# Mosfets.net
KiCad netlist of a schematic drawn in Altium Designer
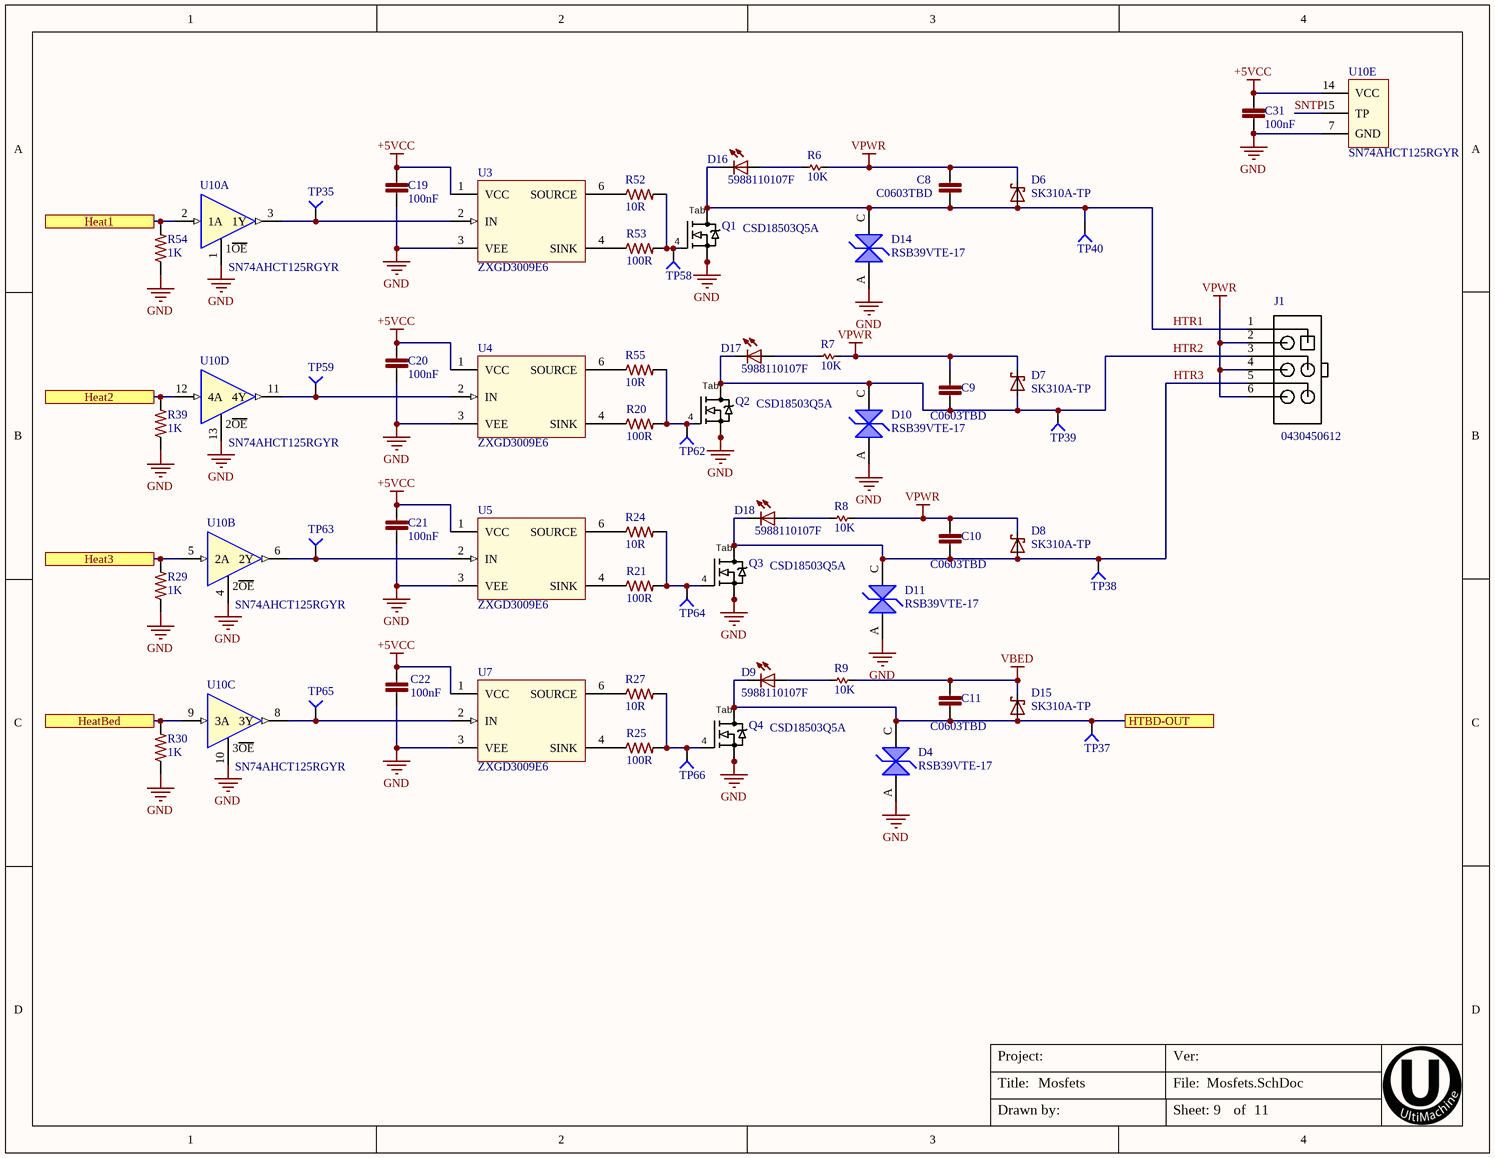
[diagram p0: Mosfets.SchDoc]

(export (version "E")
  (design (tool "Eeschema 10.0.6"))
  (components
    (comp (ref "C8")
      (value "C0603TBD")
      (footprint "C0603")
      (description "Capacitor Non Polarized")
      (fields (field (name "PART") "DNI-C0603TBD"))
      (libsource (lib "3Delight") (part "C0603TBD"))
    )
    (comp (ref "C9")
      (value "C0603TBD")
      (footprint "C0603")
      (description "Capacitor Non Polarized")
      (fields (field (name "PART") "DNI-C0603TBD"))
      (libsource (lib "3Delight") (part "C0603TBD"))
    )
    (comp (ref "C10")
      (value "C0603TBD")
      (footprint "C0603")
      (description "Capacitor Non Polarized")
      (fields (field (name "PART") "DNI-C0603TBD"))
      (libsource (lib "3Delight") (part "C0603TBD"))
    )
    (comp (ref "C11")
      (value "C0603TBD")
      (footprint "C0603")
      (description "Capacitor Non Polarized")
      (fields (field (name "PART") "DNI-C0603TBD"))
      (libsource (lib "3Delight") (part "C0603TBD"))
    )
    (comp (ref "C19")
      (value "100nF")
      (footprint "C0402")
      (description "CAP CER 0402 100nF 16V 10% X7R")
      (fields (field (name "MANUFACTURER") "Murata") (field (name "PART") "GRM155R71C104KA88D"))
      (libsource (lib "") (part "GRM155R71C104KA88D_1"))
    )
    (comp (ref "C20")
      (value "100nF")
      (footprint "C0402")
      (description "CAP CER 0402 100nF 16V 10% X7R")
      (fields (field (name "MANUFACTURER") "Murata") (field (name "PART") "GRM155R71C104KA88D"))
      (libsource (lib "") (part "GRM155R71C104KA88D_1"))
    )
    (comp (ref "C21")
      (value "100nF")
      (footprint "C0402")
      (description "CAP CER 0402 100nF 16V 10% X7R")
      (fields (field (name "MANUFACTURER") "Murata") (field (name "PART") "GRM155R71C104KA88D"))
      (libsource (lib "") (part "GRM155R71C104KA88D_1"))
    )
    (comp (ref "C22")
      (value "100nF")
      (footprint "C0402")
      (description "CAP CER 0402 100nF 16V 10% X7R")
      (fields (field (name "MANUFACTURER") "Murata") (field (name "PART") "GRM155R71C104KA88D"))
      (libsource (lib "3Delight") (part "GRM155R71C104KA88D"))
    )
    (comp (ref "C31")
      (value "100nF")
      (footprint "C0402")
      (description "CAP CER 0402 100nF 16V 10% X7R")
      (fields (field (name "MANUFACTURER") "Murata") (field (name "PART") "GRM155R71C104KA88D"))
      (libsource (lib "") (part "GRM155R71C104KA88D_1"))
    )
    (comp (ref "D4")
      (value "RSB39VTE-17")
      (footprint "SOD323-R")
      (description "DIODE TVS")
      (fields (field (name "MANUFACTURER") "Rohm") (field (name "TOLERANCE") "-NA-"))
      (libsource (lib "3Delight") (part "RSB39VTE-17"))
    )
    (comp (ref "D6")
      (value "SK310A-TP")
      (footprint "SMA-SM")
      (description "DIODE Schottky 3A SMA")
      (fields (field (name "MANUFACTURER") "MCC") (field (name "PART") "SK310A"))
      (libsource (lib "Archim_0.4") (part "SK310A"))
    )
    (comp (ref "D7")
      (value "SK310A-TP")
      (footprint "SMA-SM")
      (description "DIODE Schottky 3A SMA")
      (fields (field (name "MANUFACTURER") "MCC") (field (name "PART") "SK310A"))
      (libsource (lib "Archim_0.4") (part "SK310A"))
    )
    (comp (ref "D8")
      (value "SK310A-TP")
      (footprint "SMA-SM")
      (description "DIODE Schottky 3A SMA")
      (fields (field (name "MANUFACTURER") "MCC") (field (name "PART") "SK310A"))
      (libsource (lib "Archim_0.4") (part "SK310A"))
    )
    (comp (ref "D9")
      (value "Red")
      (footprint "LED2012120")
      (description "LED 0805 Red")
      (fields
        (field (name "MANUFACTURER") "Dialight")
        (field (name "PART") "5988110107F")
        (field (name "TOLERANCE") "-NA-")
      )
      (libsource (lib "3Delight") (part "5988110107F"))
    )
    (comp (ref "D10")
      (value "RSB39VTE-17")
      (footprint "SOD323-R")
      (description "DIODE TVS")
      (fields (field (name "MANUFACTURER") "Rohm") (field (name "TOLERANCE") "-NA-"))
      (libsource (lib "3Delight") (part "RSB39VTE-17"))
    )
    (comp (ref "D11")
      (value "RSB39VTE-17")
      (footprint "SOD323-R")
      (description "DIODE TVS")
      (fields (field (name "MANUFACTURER") "Rohm") (field (name "TOLERANCE") "-NA-"))
      (libsource (lib "3Delight") (part "RSB39VTE-17"))
    )
    (comp (ref "D14")
      (value "RSB39VTE-17")
      (footprint "SOD323-R")
      (description "DIODE TVS")
      (fields (field (name "MANUFACTURER") "Rohm") (field (name "TOLERANCE") "-NA-"))
      (libsource (lib "3Delight") (part "RSB39VTE-17"))
    )
    (comp (ref "D15")
      (value "SK310A-TP")
      (footprint "SMA-SM")
      (description "DIODE Schottky 3A SMA")
      (fields (field (name "MANUFACTURER") "MCC") (field (name "PART") "SK310A"))
      (libsource (lib "Archim_0.4") (part "SK310A"))
    )
    (comp (ref "D16")
      (value "Red")
      (footprint "LED2012120")
      (description "LED 0805 Red")
      (fields
        (field (name "MANUFACTURER") "Dialight")
        (field (name "PART") "5988110107F")
        (field (name "TOLERANCE") "-NA-")
      )
      (libsource (lib "3Delight") (part "5988110107F"))
    )
    (comp (ref "D17")
      (value "Red")
      (footprint "LED2012120")
      (description "LED 0805 Red")
      (fields
        (field (name "MANUFACTURER") "Dialight")
        (field (name "PART") "5988110107F")
        (field (name "TOLERANCE") "-NA-")
      )
      (libsource (lib "3Delight") (part "5988110107F"))
    )
    (comp (ref "D18")
      (value "Red")
      (footprint "LED2012120")
      (description "LED 0805 Red")
      (fields
        (field (name "MANUFACTURER") "Dialight")
        (field (name "PART") "5988110107F")
        (field (name "TOLERANCE") "-NA-")
      )
      (libsource (lib "3Delight") (part "5988110107F"))
    )
    (comp (ref "J1")
      (value "0430450612")
      (footprint "43045-0612")
      (description "Conn - 3mm Pitch Fixed")
      (fields (field (name "MANUFACTURER") "Molex"))
      (libsource (lib "Connectors") (part "Micro-Fit THT 6pos 3mm"))
    )
    (comp (ref "Q1")
      (value "CSD18503Q5A")
      (footprint "SOT669_Universal")
      (description "MOSFET N-CH 40V 100A 8VSON")
      (fields (field (name "MANUFACTURER") "TI"))
      (libsource (lib "Transistors") (part "CSD18503Q5A"))
    )
    (comp (ref "Q2")
      (value "CSD18503Q5A")
      (footprint "SOT669_Universal")
      (description "MOSFET N-CH 40V 100A 8VSON")
      (fields (field (name "MANUFACTURER") "TI"))
      (libsource (lib "Transistors") (part "CSD18503Q5A"))
    )
    (comp (ref "Q3")
      (value "CSD18503Q5A")
      (footprint "SOT669_Universal")
      (description "MOSFET N-CH 40V 100A 8VSON")
      (fields (field (name "MANUFACTURER") "TI"))
      (libsource (lib "Transistors") (part "CSD18503Q5A"))
    )
    (comp (ref "Q4")
      (value "CSD18503Q5A")
      (footprint "SOT669_Universal")
      (description "MOSFET N-CH 40V 100A 8VSON")
      (fields (field (name "MANUFACTURER") "TI"))
      (libsource (lib "Transistors") (part "CSD18503Q5A"))
    )
    (comp (ref "R6")
      (value "10K")
      (footprint "R0402")
      (description "RES SMD 10K OHM 1% 1/16W 0402")
      (fields (field (name "MANUFACTURER") "Yageo") (field (name "PART") "RC0402FR-0710KP"))
      (libsource (lib "Resistors") (part "10k 1% 0402"))
    )
    (comp (ref "R7")
      (value "10K")
      (footprint "R0402")
      (description "RES SMD 10K OHM 1% 1/16W 0402")
      (fields (field (name "MANUFACTURER") "Yageo") (field (name "PART") "RC0402FR-0710KP"))
      (libsource (lib "Resistors") (part "10k 1% 0402"))
    )
    (comp (ref "R8")
      (value "10K")
      (footprint "R0402")
      (description "RES SMD 10K OHM 1% 1/16W 0402")
      (fields (field (name "MANUFACTURER") "Yageo") (field (name "PART") "RC0402FR-0710KP"))
      (libsource (lib "Resistors") (part "10k 1% 0402"))
    )
    (comp (ref "R9")
      (value "10K")
      (footprint "R0402")
      (description "RES SMD 10K OHM 1% 1/16W 0402")
      (fields (field (name "MANUFACTURER") "Yageo") (field (name "PART") "RC0402FR-0710KP"))
      (libsource (lib "Resistors") (part "10k 1% 0402"))
    )
    (comp (ref "R20")
      (value "100R")
      (footprint "R0402")
      (description "RES SMD 100 OHM 1% 1/16W 0402")
      (fields (field (name "MANUFACTURER") "Yageo") (field (name "PART") "RC0402FR-07100RL"))
      (libsource (lib "Archim") (part "RES 100R 0402 1%"))
    )
    (comp (ref "R21")
      (value "100R")
      (footprint "R0402")
      (description "RES SMD 100 OHM 1% 1/16W 0402")
      (fields (field (name "MANUFACTURER") "Yageo") (field (name "PART") "RC0402FR-07100RL"))
      (libsource (lib "Archim") (part "RES 100R 0402 1%"))
    )
    (comp (ref "R24")
      (value "10R")
      (footprint "R0402")
      (description "RES SMD 10 OHM 1% 1/16W 0402")
      (fields (field (name "MANUFACTURER") "Yageo") (field (name "PART") "RC0402FR-0710RL"))
      (libsource (lib "3Delight") (part "RC0402FR-0710RL"))
    )
    (comp (ref "R25")
      (value "100R")
      (footprint "R0402")
      (description "RES SMD 100 OHM 1% 1/16W 0402")
      (fields (field (name "MANUFACTURER") "Yageo") (field (name "PART") "RC0402FR-07100RL"))
      (libsource (lib "Archim") (part "RES 100R 0402 1%"))
    )
    (comp (ref "R27")
      (value "10R")
      (footprint "R0402")
      (description "RES SMD 10 OHM 1% 1/16W 0402")
      (fields (field (name "MANUFACTURER") "Yageo") (field (name "PART") "RC0402FR-0710RL"))
      (libsource (lib "3Delight") (part "RC0402FR-0710RL"))
    )
    (comp (ref "R29")
      (value "1K")
      (footprint "R0402")
      (description "RES SMD 1K OHM 1% 1/16W 0402")
      (fields (field (name "MANUFACTURER") "Yageo") (field (name "PART") "RC0402FR-0710KP"))
      (libsource (lib "3Delight") (part "RC0402FR-0710KP"))
    )
    (comp (ref "R30")
      (value "1K")
      (footprint "R0402")
      (description "RES SMD 1K OHM 1% 1/16W 0402")
      (fields (field (name "MANUFACTURER") "Yageo") (field (name "PART") "RC0402FR-0710KP"))
      (libsource (lib "3Delight") (part "RC0402FR-0710KP"))
    )
    (comp (ref "R39")
      (value "1K")
      (footprint "R0402")
      (description "RES SMD 1K OHM 1% 1/16W 0402")
      (fields (field (name "MANUFACTURER") "Yageo") (field (name "PART") "RC0402FR-0710KP"))
      (libsource (lib "3Delight") (part "RC0402FR-0710KP"))
    )
    (comp (ref "R52")
      (value "10R")
      (footprint "R0402")
      (description "RES SMD 10 OHM 1% 1/16W 0402")
      (fields (field (name "MANUFACTURER") "Yageo") (field (name "PART") "RC0402FR-0710RL"))
      (libsource (lib "3Delight") (part "RC0402FR-0710RL"))
    )
    (comp (ref "R53")
      (value "100R")
      (footprint "R0402")
      (description "RES SMD 100 OHM 1% 1/16W 0402")
      (fields (field (name "MANUFACTURER") "Yageo") (field (name "PART") "RC0402FR-07100RL"))
      (libsource (lib "Archim") (part "RES 100R 0402 1%"))
    )
    (comp (ref "R54")
      (value "1K")
      (footprint "R0402")
      (description "RES SMD 1K OHM 1% 1/16W 0402")
      (fields (field (name "MANUFACTURER") "Yageo") (field (name "PART") "RC0402FR-0710KP"))
      (libsource (lib "3Delight") (part "RC0402FR-0710KP"))
    )
    (comp (ref "R55")
      (value "10R")
      (footprint "R0402")
      (description "RES SMD 10 OHM 1% 1/16W 0402")
      (fields (field (name "MANUFACTURER") "Yageo") (field (name "PART") "RC0402FR-0710RL"))
      (libsource (lib "3Delight") (part "RC0402FR-0710RL"))
    )
    (comp (ref "TP35")
      (value "TP4")
      (footprint "TP-2")
      (description "Socket")
      (fields (field (name "PART") "NOTAPART-Testpoint"))
      (libsource (lib "Archim") (part "Socket"))
    )
    (comp (ref "TP37")
      (value "TP4")
      (footprint "TP-2")
      (description "Socket")
      (fields (field (name "PART") "NOTAPART-Testpoint"))
      (libsource (lib "Archim") (part "Socket"))
    )
    (comp (ref "TP38")
      (value "TP4")
      (footprint "TP-2")
      (description "Socket")
      (fields (field (name "PART") "NOTAPART-Testpoint"))
      (libsource (lib "Archim") (part "Socket"))
    )
    (comp (ref "TP39")
      (value "TP4")
      (footprint "TP-2")
      (description "Socket")
      (fields (field (name "PART") "NOTAPART-Testpoint"))
      (libsource (lib "Archim") (part "Socket"))
    )
    (comp (ref "TP40")
      (value "TP4")
      (footprint "TP-2")
      (description "Socket")
      (fields (field (name "PART") "NOTAPART-Testpoint"))
      (libsource (lib "Archim") (part "Socket"))
    )
    (comp (ref "TP58")
      (value "TP4")
      (footprint "TP-2")
      (description "Socket")
      (fields (field (name "PART") "NOTAPART-Testpoint"))
      (libsource (lib "Archim") (part "Socket"))
    )
    (comp (ref "TP59")
      (value "TP4")
      (footprint "TP-2")
      (description "Socket")
      (fields (field (name "PART") "NOTAPART-Testpoint"))
      (libsource (lib "Archim") (part "Socket"))
    )
    (comp (ref "TP62")
      (value "TP4")
      (footprint "TP-2")
      (description "Socket")
      (fields (field (name "PART") "NOTAPART-Testpoint"))
      (libsource (lib "Archim") (part "Socket"))
    )
    (comp (ref "TP63")
      (value "TP4")
      (footprint "TP-2")
      (description "Socket")
      (fields (field (name "PART") "NOTAPART-Testpoint"))
      (libsource (lib "Archim") (part "Socket"))
    )
    (comp (ref "TP64")
      (value "TP4")
      (footprint "TP-2")
      (description "Socket")
      (fields (field (name "PART") "NOTAPART-Testpoint"))
      (libsource (lib "Archim") (part "Socket"))
    )
    (comp (ref "TP65")
      (value "TP4")
      (footprint "TP-2")
      (description "Socket")
      (fields (field (name "PART") "NOTAPART-Testpoint"))
      (libsource (lib "Archim") (part "Socket"))
    )
    (comp (ref "TP66")
      (value "TP4")
      (footprint "TP-2")
      (description "Socket")
      (fields (field (name "PART") "NOTAPART-Testpoint"))
      (libsource (lib "Archim") (part "Socket"))
    )
    (comp (ref "U3")
      (value "ZXGD3009E6")
      (footprint "SOT26P285X140-6L")
      (description "MOSFET DRVR 3A 1-OUT High Speed Non-Inv6-Pin SOT-26 T/R")
      (fields (field (name "MANUFACTURER") "Diodes Incorporated") (field (name "PART") "ZXGD3009E6TA"))
      (libsource (lib "3Delight") (part "ZXGD3009E6"))
    )
    (comp (ref "U4")
      (value "ZXGD3009E6")
      (footprint "SOT26P285X140-6L")
      (description "MOSFET DRVR 3A 1-OUT High Speed Non-Inv6-Pin SOT-26 T/R")
      (fields (field (name "MANUFACTURER") "Diodes Incorporated") (field (name "PART") "ZXGD3009E6TA"))
      (libsource (lib "3Delight") (part "ZXGD3009E6"))
    )
    (comp (ref "U5")
      (value "ZXGD3009E6")
      (footprint "SOT26P285X140-6L")
      (description "MOSFET DRVR 3A 1-OUT High Speed Non-Inv6-Pin SOT-26 T/R")
      (fields (field (name "MANUFACTURER") "Diodes Incorporated") (field (name "PART") "ZXGD3009E6TA"))
      (libsource (lib "3Delight") (part "ZXGD3009E6"))
    )
    (comp (ref "U7")
      (value "ZXGD3009E6")
      (footprint "SOT26P285X140-6L")
      (description "MOSFET DRVR 3A 1-OUT High Speed Non-Inv6-Pin SOT-26 T/R")
      (fields (field (name "MANUFACTURER") "Diodes Incorporated") (field (name "PART") "ZXGD3009E6TA"))
      (libsource (lib "3Delight") (part "ZXGD3009E6"))
    )
    (comp (ref "U10")
      (value "SN74AHCT125RGYR")
      (footprint "QFN50P350X350X100_RGY_S-PVQFN-N14")
      (description "Quadruple Bus Buffer Gates With 3-State Outputs 14-VQFN -40 to 125")
      (fields (field (name "MANUFACTURER") "Texas Instruments") (field (name "TOLERANCE") "-NA-"))
      (libsource (lib "3Delight") (part "SN74AHCT125"))
    )
  )
  (nets
    (net (code "1") (name "+5VCC") (class "Default")
      (node (ref "C19") (pin "2") (pinfunction "2_2") (pintype "passive"))
      (node (ref "C20") (pin "2") (pinfunction "2_2") (pintype "passive"))
      (node (ref "C21") (pin "2") (pinfunction "2_2") (pintype "passive"))
      (node (ref "C22") (pin "1") (pinfunction "1_1") (pintype "passive"))
      (node (ref "C31") (pin "2") (pinfunction "2_2") (pintype "passive"))
      (node (ref "U10") (pin "14") (pinfunction "VCC_14") (pintype "power_in"))
      (node (ref "U3") (pin "1") (pinfunction "VCC_1") (pintype "power_in"))
      (node (ref "U4") (pin "1") (pinfunction "VCC_1") (pintype "power_in"))
      (node (ref "U5") (pin "1") (pinfunction "VCC_1") (pintype "power_in"))
      (node (ref "U7") (pin "1") (pinfunction "VCC_1") (pintype "power_in"))
    )
    (net (code "2") (name "/HTBD-OUT") (class "Default")
      (node (ref "C11") (pin "2") (pinfunction "2_2") (pintype "passive"))
      (node (ref "D15") (pin "A") (pinfunction "A_A") (pintype "passive"))
      (node (ref "D4") (pin "C") (pinfunction "C_C") (pintype "power_in"))
      (node (ref "D9") (pin "C") (pinfunction "C_C") (pintype "passive"))
      (node (ref "Q4") (pin "TAB") (pinfunction "D_TAB") (pintype "passive"))
      (node (ref "TP37") (pin "1") (pinfunction "1_1") (pintype "passive"))
    )
    (net (code "3") (name "/HTR1") (class "Default")
      (node (ref "C8") (pin "2") (pinfunction "2_2") (pintype "passive"))
      (node (ref "D14") (pin "C") (pinfunction "C_C") (pintype "power_in"))
      (node (ref "D16") (pin "C") (pinfunction "C_C") (pintype "passive"))
      (node (ref "D6") (pin "A") (pinfunction "A_A") (pintype "passive"))
      (node (ref "J1") (pin "1") (pinfunction "1_1") (pintype "power_in"))
      (node (ref "Q1") (pin "TAB") (pinfunction "D_TAB") (pintype "passive"))
      (node (ref "TP40") (pin "1") (pinfunction "1_1") (pintype "passive"))
    )
    (net (code "4") (name "/HTR2") (class "Default")
      (node (ref "C9") (pin "2") (pinfunction "2_2") (pintype "passive"))
      (node (ref "D10") (pin "C") (pinfunction "C_C") (pintype "power_in"))
      (node (ref "D17") (pin "C") (pinfunction "C_C") (pintype "passive"))
      (node (ref "D7") (pin "A") (pinfunction "A_A") (pintype "passive"))
      (node (ref "J1") (pin "3") (pinfunction "3_3") (pintype "power_in"))
      (node (ref "Q2") (pin "TAB") (pinfunction "D_TAB") (pintype "passive"))
      (node (ref "TP39") (pin "1") (pinfunction "1_1") (pintype "passive"))
    )
    (net (code "5") (name "/HTR3") (class "Default")
      (node (ref "C10") (pin "2") (pinfunction "2_2") (pintype "passive"))
      (node (ref "D11") (pin "C") (pinfunction "C_C") (pintype "power_in"))
      (node (ref "D18") (pin "C") (pinfunction "C_C") (pintype "passive"))
      (node (ref "D8") (pin "A") (pinfunction "A_A") (pintype "passive"))
      (node (ref "J1") (pin "5") (pinfunction "5_5") (pintype "power_in"))
      (node (ref "Q3") (pin "TAB") (pinfunction "D_TAB") (pintype "passive"))
      (node (ref "TP38") (pin "1") (pinfunction "1_1") (pintype "passive"))
    )
    (net (code "6") (name "/Heat1") (class "Default")
      (node (ref "R54") (pin "2") (pinfunction "2_2") (pintype "passive"))
      (node (ref "U10") (pin "2") (pinfunction "1A_2") (pintype "input"))
    )
    (net (code "7") (name "/Heat2") (class "Default")
      (node (ref "R39") (pin "2") (pinfunction "2_2") (pintype "passive"))
      (node (ref "U10") (pin "12") (pinfunction "4A_12") (pintype "input"))
    )
    (net (code "8") (name "/Heat3") (class "Default")
      (node (ref "R29") (pin "2") (pinfunction "2_2") (pintype "passive"))
      (node (ref "U10") (pin "5") (pinfunction "2A_5") (pintype "input"))
    )
    (net (code "9") (name "/HeatBed") (class "Default")
      (node (ref "R30") (pin "2") (pinfunction "2_2") (pintype "passive"))
      (node (ref "U10") (pin "9") (pinfunction "3A_9") (pintype "input"))
    )
    (net (code "10") (name "/SNTP") (class "Default")
      (node (ref "U10") (pin "15") (pinfunction "TP_15") (pintype "power_in"))
    )
    (net (code "11") (name "GND") (class "Default")
      (node (ref "C19") (pin "1") (pinfunction "1_1") (pintype "passive"))
      (node (ref "C20") (pin "1") (pinfunction "1_1") (pintype "passive"))
      (node (ref "C21") (pin "1") (pinfunction "1_1") (pintype "passive"))
      (node (ref "C22") (pin "2") (pinfunction "2_2") (pintype "passive"))
      (node (ref "C31") (pin "1") (pinfunction "1_1") (pintype "passive"))
      (node (ref "D10") (pin "A") (pinfunction "A_A") (pintype "power_in"))
      (node (ref "D11") (pin "A") (pinfunction "A_A") (pintype "power_in"))
      (node (ref "D14") (pin "A") (pinfunction "A_A") (pintype "power_in"))
      (node (ref "D4") (pin "A") (pinfunction "A_A") (pintype "power_in"))
      (node (ref "Q1") (pin "1") (pinfunction "S_1") (pintype "passive"))
      (node (ref "Q1") (pin "2") (pinfunction "S_2") (pintype "passive"))
      (node (ref "Q1") (pin "3") (pinfunction "S_3") (pintype "passive"))
      (node (ref "Q2") (pin "1") (pinfunction "S_1") (pintype "passive"))
      (node (ref "Q2") (pin "2") (pinfunction "S_2") (pintype "passive"))
      (node (ref "Q2") (pin "3") (pinfunction "S_3") (pintype "passive"))
      (node (ref "Q3") (pin "1") (pinfunction "S_1") (pintype "passive"))
      (node (ref "Q3") (pin "2") (pinfunction "S_2") (pintype "passive"))
      (node (ref "Q3") (pin "3") (pinfunction "S_3") (pintype "passive"))
      (node (ref "Q4") (pin "1") (pinfunction "S_1") (pintype "passive"))
      (node (ref "Q4") (pin "2") (pinfunction "S_2") (pintype "passive"))
      (node (ref "Q4") (pin "3") (pinfunction "S_3") (pintype "passive"))
      (node (ref "R29") (pin "1") (pinfunction "1_1") (pintype "passive"))
      (node (ref "R30") (pin "1") (pinfunction "1_1") (pintype "passive"))
      (node (ref "R39") (pin "1") (pinfunction "1_1") (pintype "passive"))
      (node (ref "R54") (pin "1") (pinfunction "1_1") (pintype "passive"))
      (node (ref "U10") (pin "1") (pinfunction "1OE_1") (pintype "power_in"))
      (node (ref "U10") (pin "10") (pinfunction "3OE_10") (pintype "power_in"))
      (node (ref "U10") (pin "13") (pinfunction "4OE_13") (pintype "power_in"))
      (node (ref "U10") (pin "4") (pinfunction "2OE_4") (pintype "power_in"))
      (node (ref "U10") (pin "7") (pinfunction "GND_7") (pintype "power_in"))
      (node (ref "U3") (pin "3") (pinfunction "VEE_3") (pintype "power_in"))
      (node (ref "U4") (pin "3") (pinfunction "VEE_3") (pintype "power_in"))
      (node (ref "U5") (pin "3") (pinfunction "VEE_3") (pintype "power_in"))
      (node (ref "U7") (pin "3") (pinfunction "VEE_3") (pintype "power_in"))
    )
    (net (code "12") (name "Net-(D9-PadA)") (class "Default")
      (node (ref "D9") (pin "A") (pinfunction "A_A") (pintype "passive"))
      (node (ref "R9") (pin "1") (pinfunction "1_1") (pintype "passive"))
    )
    (net (code "13") (name "Net-(D16-PadA)") (class "Default")
      (node (ref "D16") (pin "A") (pinfunction "A_A") (pintype "passive"))
      (node (ref "R6") (pin "1") (pinfunction "1_1") (pintype "passive"))
    )
    (net (code "14") (name "Net-(D17-PadA)") (class "Default")
      (node (ref "D17") (pin "A") (pinfunction "A_A") (pintype "passive"))
      (node (ref "R7") (pin "1") (pinfunction "1_1") (pintype "passive"))
    )
    (net (code "15") (name "Net-(D18-PadA)") (class "Default")
      (node (ref "D18") (pin "A") (pinfunction "A_A") (pintype "passive"))
      (node (ref "R8") (pin "1") (pinfunction "1_1") (pintype "passive"))
    )
    (net (code "16") (name "Net-(Q1-G)") (class "Default")
      (node (ref "Q1") (pin "4") (pinfunction "G_4") (pintype "passive"))
      (node (ref "R52") (pin "2") (pinfunction "2_2") (pintype "passive"))
      (node (ref "R53") (pin "2") (pinfunction "2_2") (pintype "passive"))
      (node (ref "TP58") (pin "1") (pinfunction "1_1") (pintype "passive"))
    )
    (net (code "17") (name "Net-(Q2-G)") (class "Default")
      (node (ref "Q2") (pin "4") (pinfunction "G_4") (pintype "passive"))
      (node (ref "R20") (pin "2") (pinfunction "2_2") (pintype "passive"))
      (node (ref "R55") (pin "2") (pinfunction "2_2") (pintype "passive"))
      (node (ref "TP62") (pin "1") (pinfunction "1_1") (pintype "passive"))
    )
    (net (code "18") (name "Net-(Q3-G)") (class "Default")
      (node (ref "Q3") (pin "4") (pinfunction "G_4") (pintype "passive"))
      (node (ref "R21") (pin "2") (pinfunction "2_2") (pintype "passive"))
      (node (ref "R24") (pin "2") (pinfunction "2_2") (pintype "passive"))
      (node (ref "TP64") (pin "1") (pinfunction "1_1") (pintype "passive"))
    )
    (net (code "19") (name "Net-(Q4-G)") (class "Default")
      (node (ref "Q4") (pin "4") (pinfunction "G_4") (pintype "passive"))
      (node (ref "R25") (pin "2") (pinfunction "2_2") (pintype "passive"))
      (node (ref "R27") (pin "2") (pinfunction "2_2") (pintype "passive"))
      (node (ref "TP66") (pin "1") (pinfunction "1_1") (pintype "passive"))
    )
    (net (code "20") (name "Net-(U3-SINK)") (class "Default")
      (node (ref "R53") (pin "1") (pinfunction "1_1") (pintype "passive"))
      (node (ref "U3") (pin "4") (pinfunction "SINK_4") (pintype "power_in"))
    )
    (net (code "21") (name "Net-(U3-SOURCE)") (class "Default")
      (node (ref "R52") (pin "1") (pinfunction "1_1") (pintype "passive"))
      (node (ref "U3") (pin "6") (pinfunction "SOURCE_6") (pintype "power_in"))
    )
    (net (code "22") (name "Net-(U4-SINK)") (class "Default")
      (node (ref "R20") (pin "1") (pinfunction "1_1") (pintype "passive"))
      (node (ref "U4") (pin "4") (pinfunction "SINK_4") (pintype "power_in"))
    )
    (net (code "23") (name "Net-(U4-SOURCE)") (class "Default")
      (node (ref "R55") (pin "1") (pinfunction "1_1") (pintype "passive"))
      (node (ref "U4") (pin "6") (pinfunction "SOURCE_6") (pintype "power_in"))
    )
    (net (code "24") (name "Net-(U5-SINK)") (class "Default")
      (node (ref "R21") (pin "1") (pinfunction "1_1") (pintype "passive"))
      (node (ref "U5") (pin "4") (pinfunction "SINK_4") (pintype "power_in"))
    )
    (net (code "25") (name "Net-(U5-SOURCE)") (class "Default")
      (node (ref "R24") (pin "1") (pinfunction "1_1") (pintype "passive"))
      (node (ref "U5") (pin "6") (pinfunction "SOURCE_6") (pintype "power_in"))
    )
    (net (code "26") (name "Net-(U7-SINK)") (class "Default")
      (node (ref "R25") (pin "1") (pinfunction "1_1") (pintype "passive"))
      (node (ref "U7") (pin "4") (pinfunction "SINK_4") (pintype "power_in"))
    )
    (net (code "27") (name "Net-(U7-SOURCE)") (class "Default")
      (node (ref "R27") (pin "1") (pinfunction "1_1") (pintype "passive"))
      (node (ref "U7") (pin "6") (pinfunction "SOURCE_6") (pintype "power_in"))
    )
    (net (code "28") (name "Net-(U10A-1Y)") (class "Default")
      (node (ref "TP35") (pin "1") (pinfunction "1_1") (pintype "passive"))
      (node (ref "U10") (pin "3") (pinfunction "1Y_3") (pintype "output"))
      (node (ref "U3") (pin "2") (pinfunction "IN_2") (pintype "input"))
    )
    (net (code "29") (name "Net-(U10B-2Y)") (class "Default")
      (node (ref "TP63") (pin "1") (pinfunction "1_1") (pintype "passive"))
      (node (ref "U10") (pin "6") (pinfunction "2Y_6") (pintype "output"))
      (node (ref "U5") (pin "2") (pinfunction "IN_2") (pintype "input"))
    )
    (net (code "30") (name "Net-(U10C-3Y)") (class "Default")
      (node (ref "TP65") (pin "1") (pinfunction "1_1") (pintype "passive"))
      (node (ref "U10") (pin "8") (pinfunction "3Y_8") (pintype "output"))
      (node (ref "U7") (pin "2") (pinfunction "IN_2") (pintype "input"))
    )
    (net (code "31") (name "Net-(U10D-4Y)") (class "Default")
      (node (ref "TP59") (pin "1") (pinfunction "1_1") (pintype "passive"))
      (node (ref "U10") (pin "11") (pinfunction "4Y_11") (pintype "output"))
      (node (ref "U4") (pin "2") (pinfunction "IN_2") (pintype "input"))
    )
    (net (code "32") (name "VBED") (class "Default")
      (node (ref "C11") (pin "1") (pinfunction "1_1") (pintype "passive"))
      (node (ref "D15") (pin "C") (pinfunction "C_C") (pintype "passive"))
      (node (ref "R9") (pin "2") (pinfunction "2_2") (pintype "passive"))
    )
    (net (code "33") (name "VPWR") (class "Default")
      (node (ref "C10") (pin "1") (pinfunction "1_1") (pintype "passive"))
      (node (ref "C8") (pin "1") (pinfunction "1_1") (pintype "passive"))
      (node (ref "C9") (pin "1") (pinfunction "1_1") (pintype "passive"))
      (node (ref "D6") (pin "C") (pinfunction "C_C") (pintype "passive"))
      (node (ref "D7") (pin "C") (pinfunction "C_C") (pintype "passive"))
      (node (ref "D8") (pin "C") (pinfunction "C_C") (pintype "passive"))
      (node (ref "J1") (pin "2") (pinfunction "2_2") (pintype "power_in"))
      (node (ref "J1") (pin "4") (pinfunction "4_4") (pintype "power_in"))
      (node (ref "J1") (pin "6") (pinfunction "6_6") (pintype "power_in"))
      (node (ref "R6") (pin "2") (pinfunction "2_2") (pintype "passive"))
      (node (ref "R7") (pin "2") (pinfunction "2_2") (pintype "passive"))
      (node (ref "R8") (pin "2") (pinfunction "2_2") (pintype "passive"))
    )
  )
)
